# Juglans.net
KiCad netlist of a schematic drawn in Altium Designer
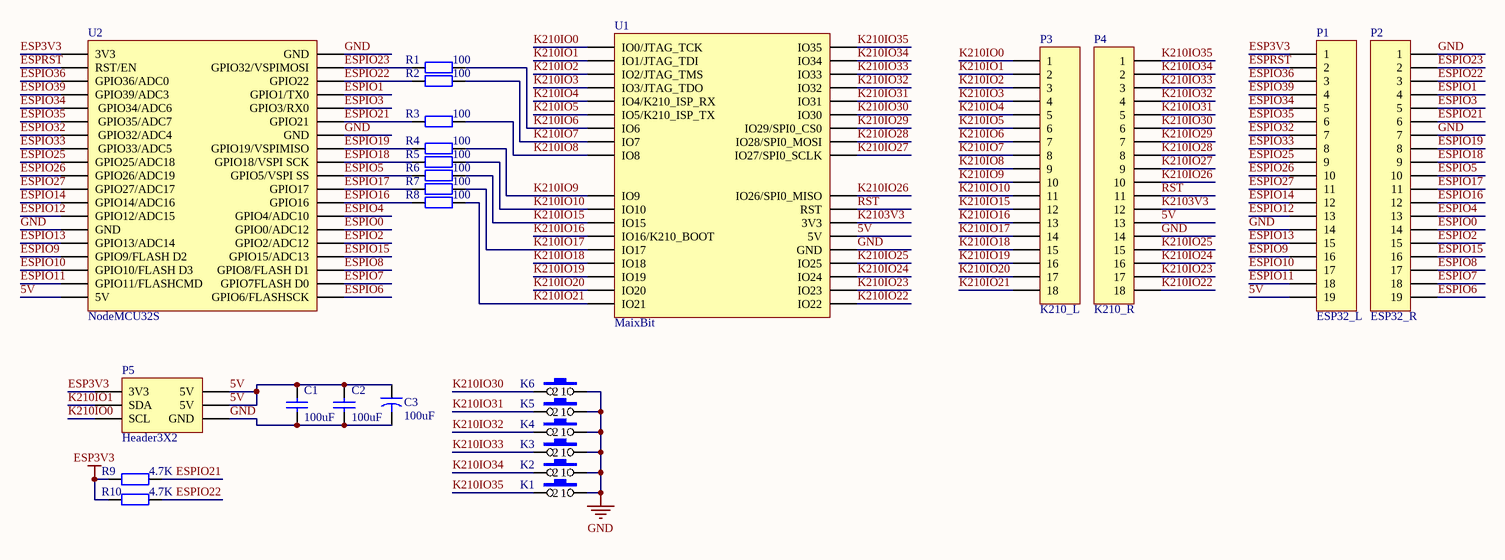
[diagram p0: Juglans.SchDoc]

(export (version "E")
  (design (tool "Eeschema 10.0.6"))
  (components
    (comp (ref "C1")
      (value "100uF")
      (footprint "C 1206_L")
      (description "Capacitor")
      (fields (field (name "Comment") "Cap") (field (name "PUBLISHER") "Altium Limited"))
      (libsource (lib "Miscellaneous Devices") (part "Cap"))
    )
    (comp (ref "C2")
      (value "100uF")
      (footprint "C 1206_L")
      (description "Capacitor")
      (fields (field (name "Comment") "Cap") (field (name "PUBLISHER") "Altium Limited"))
      (libsource (lib "Miscellaneous Devices") (part "Cap"))
    )
    (comp (ref "C3")
      (value "100uF")
      (footprint "CAP")
      (description "Capacitor")
      (fields (field (name "Comment") "Cap2") (field (name "PUBLISHER") "Altium Limited"))
      (libsource (lib "Miscellaneous Devices") (part "Cap2"))
    )
    (comp (ref "K1") (value "KEY?") (footprint "SW-PB2-S") (libsource (lib "Connectors") (part "SW-PB2")))
    (comp (ref "K2") (value "KEY?") (footprint "SW-PB2-S") (libsource (lib "Connectors") (part "SW-PB2")))
    (comp (ref "K3") (value "KEY?") (footprint "SW-PB2-S") (libsource (lib "Connectors") (part "SW-PB2")))
    (comp (ref "K4") (value "KEY?") (footprint "SW-PB2-S") (libsource (lib "Connectors") (part "SW-PB2")))
    (comp (ref "K5") (value "KEY?") (footprint "SW-PB2-S") (libsource (lib "Connectors") (part "SW-PB2")))
    (comp (ref "K6") (value "KEY?") (footprint "SW-PB2-S") (libsource (lib "Connectors") (part "SW-PB2")))
    (comp (ref "P1")
      (value "ESP32_L")
      (footprint "HDR1X19")
      (description "Header, 19-Pin")
      (fields (field (name "PUBLISHER") "Altium Limited"))
      (libsource (lib "") (part "Header 19_1"))
    )
    (comp (ref "P2")
      (value "ESP32_R")
      (footprint "HDR1X19")
      (description "Header, 19-Pin")
      (fields (field (name "PUBLISHER") "Altium Limited"))
      (libsource (lib "Miscellaneous Connectors") (part "Header 19"))
    )
    (comp (ref "P3")
      (value "K210_L")
      (footprint "HDR1X18")
      (description "Header, 18-Pin")
      (fields (field (name "PUBLISHER") "Altium Limited"))
      (libsource (lib "") (part "Header 18_1"))
    )
    (comp (ref "P4")
      (value "K210_R")
      (footprint "HDR1X18")
      (description "Header, 18-Pin")
      (fields (field (name "PUBLISHER") "Altium Limited"))
      (libsource (lib "Miscellaneous Connectors") (part "Header 18"))
    )
    (comp (ref "P5") (value "Header3X2") (footprint "Header3X2") (libsource (lib "Juglans") (part "H3X2")))
    (comp (ref "R1")
      (value "100")
      (footprint "R 0603_L")
      (description "Resistor")
      (fields (field (name "Comment") "Res2") (field (name "PUBLISHER") "Altium Limited"))
      (libsource (lib "Miscellaneous Devices") (part "Res2"))
    )
    (comp (ref "R2")
      (value "100")
      (footprint "R 0603_L")
      (description "Resistor")
      (fields (field (name "Comment") "Res2") (field (name "PUBLISHER") "Altium Limited"))
      (libsource (lib "Miscellaneous Devices") (part "Res2"))
    )
    (comp (ref "R3")
      (value "100")
      (footprint "R 0603_L")
      (description "Resistor")
      (fields (field (name "Comment") "Res2") (field (name "PUBLISHER") "Altium Limited"))
      (libsource (lib "Miscellaneous Devices") (part "Res2"))
    )
    (comp (ref "R4")
      (value "100")
      (footprint "R 0603_L")
      (description "Resistor")
      (fields (field (name "Comment") "Res2") (field (name "PUBLISHER") "Altium Limited"))
      (libsource (lib "Miscellaneous Devices") (part "Res2"))
    )
    (comp (ref "R5")
      (value "100")
      (footprint "R 0603_L")
      (description "Resistor")
      (fields (field (name "Comment") "Res2") (field (name "PUBLISHER") "Altium Limited"))
      (libsource (lib "Miscellaneous Devices") (part "Res2"))
    )
    (comp (ref "R6")
      (value "100")
      (footprint "R 0603_L")
      (description "Resistor")
      (fields (field (name "Comment") "Res2") (field (name "PUBLISHER") "Altium Limited"))
      (libsource (lib "Miscellaneous Devices") (part "Res2"))
    )
    (comp (ref "R7")
      (value "100")
      (footprint "R 0603_L")
      (description "Resistor")
      (fields (field (name "Comment") "Res2") (field (name "PUBLISHER") "Altium Limited"))
      (libsource (lib "Miscellaneous Devices") (part "Res2"))
    )
    (comp (ref "R8")
      (value "100")
      (footprint "R 0603_L")
      (description "Resistor")
      (fields (field (name "Comment") "Res2") (field (name "PUBLISHER") "Altium Limited"))
      (libsource (lib "Miscellaneous Devices") (part "Res2"))
    )
    (comp (ref "R9")
      (value "4.7K")
      (footprint "R 0603_L")
      (description "Resistor")
      (fields (field (name "Comment") "Res2") (field (name "PUBLISHER") "Altium Limited"))
      (libsource (lib "Miscellaneous Devices") (part "Res2"))
    )
    (comp (ref "R10")
      (value "4.7K")
      (footprint "R 0603_L")
      (description "Resistor")
      (fields (field (name "Comment") "Res2") (field (name "PUBLISHER") "Altium Limited"))
      (libsource (lib "Miscellaneous Devices") (part "Res2"))
    )
    (comp (ref "U1") (value "MaixBit") (footprint "MaixBit") (libsource (lib "Juglans") (part "MaixBit")))
    (comp (ref "U2")
      (value "NodeMCU32S")
      (footprint "NodeMCU32S")
      (libsource (lib "Juglans") (part "NodeMCU32S"))
    )
  )
  (nets
    (net (code "1") (name "/5V") (class "Default")
      (node (ref "C1") (pin "2") (pinfunction "2_2") (pintype "passive"))
      (node (ref "C2") (pin "2") (pinfunction "2_2") (pintype "passive"))
      (node (ref "C3") (pin "1") (pinfunction "1_1") (pintype "passive"))
      (node (ref "P1") (pin "19") (pinfunction "19_19") (pintype "passive"))
      (node (ref "P4") (pin "13") (pinfunction "13_13") (pintype "passive"))
      (node (ref "P5") (pin "2") (pinfunction "5V_2") (pintype "passive"))
      (node (ref "P5") (pin "4") (pinfunction "5V_4") (pintype "passive"))
      (node (ref "U1") (pin "23") (pinfunction "5V_23") (pintype "passive"))
      (node (ref "U2") (pin "18") (pinfunction "5V_18") (pintype "passive"))
    )
    (net (code "2") (name "/ESPIO0") (class "Default")
      (node (ref "P2") (pin "14") (pinfunction "14_14") (pintype "passive"))
      (node (ref "U2") (pin "24") (pinfunction "GPIO0/ADC12_24") (pintype "passive"))
    )
    (net (code "3") (name "/ESPIO1") (class "Default")
      (node (ref "P2") (pin "4") (pinfunction "4_4") (pintype "passive"))
      (node (ref "U2") (pin "34") (pinfunction "GPIO1/TX0_34") (pintype "passive"))
    )
    (net (code "4") (name "/ESPIO2") (class "Default")
      (node (ref "P2") (pin "15") (pinfunction "15_15") (pintype "passive"))
      (node (ref "U2") (pin "23") (pinfunction "GPIO2/ADC12_23") (pintype "passive"))
    )
    (net (code "5") (name "/ESPIO3") (class "Default")
      (node (ref "P2") (pin "5") (pinfunction "5_5") (pintype "passive"))
      (node (ref "U2") (pin "33") (pinfunction "GPIO3/RX0_33") (pintype "passive"))
    )
    (net (code "6") (name "/ESPIO4") (class "Default")
      (node (ref "P2") (pin "13") (pinfunction "13_13") (pintype "passive"))
      (node (ref "U2") (pin "25") (pinfunction "GPIO4/ADC10_25") (pintype "passive"))
    )
    (net (code "7") (name "/ESPIO5") (class "Default")
      (node (ref "P2") (pin "10") (pinfunction "10_10") (pintype "passive"))
      (node (ref "R6") (pin "2") (pinfunction "2_2") (pintype "passive"))
      (node (ref "U2") (pin "28") (pinfunction "GPIO5/VSPI_SS_28") (pintype "passive"))
    )
    (net (code "8") (name "/ESPIO6") (class "Default")
      (node (ref "P2") (pin "19") (pinfunction "19_19") (pintype "passive"))
      (node (ref "U2") (pin "19") (pinfunction "GPIO6/FLASHSCK_19") (pintype "passive"))
    )
    (net (code "9") (name "/ESPIO7") (class "Default")
      (node (ref "P2") (pin "18") (pinfunction "18_18") (pintype "passive"))
      (node (ref "U2") (pin "20") (pinfunction "GPIO7FLASH_D0_20") (pintype "passive"))
    )
    (net (code "10") (name "/ESPIO8") (class "Default")
      (node (ref "P2") (pin "17") (pinfunction "17_17") (pintype "passive"))
      (node (ref "U2") (pin "21") (pinfunction "GPIO8/FLASH_D1_21") (pintype "passive"))
    )
    (net (code "11") (name "/ESPIO9") (class "Default")
      (node (ref "P1") (pin "16") (pinfunction "16_16") (pintype "passive"))
      (node (ref "U2") (pin "15") (pinfunction "GPIO9/FLASH_D2_15") (pintype "passive"))
    )
    (net (code "12") (name "/ESPIO10") (class "Default")
      (node (ref "P1") (pin "17") (pinfunction "17_17") (pintype "passive"))
      (node (ref "U2") (pin "16") (pinfunction "GPIO10/FLASH_D3_16") (pintype "passive"))
    )
    (net (code "13") (name "/ESPIO11") (class "Default")
      (node (ref "P1") (pin "18") (pinfunction "18_18") (pintype "passive"))
      (node (ref "U2") (pin "17") (pinfunction "GPIO11/FLASHCMD_17") (pintype "passive"))
    )
    (net (code "14") (name "/ESPIO12") (class "Default")
      (node (ref "P1") (pin "13") (pinfunction "13_13") (pintype "passive"))
      (node (ref "U2") (pin "12") (pinfunction "GPIO12/ADC15_12") (pintype "passive"))
    )
    (net (code "15") (name "/ESPIO13") (class "Default")
      (node (ref "P1") (pin "15") (pinfunction "15_15") (pintype "passive"))
      (node (ref "U2") (pin "14") (pinfunction "GPIO13/ADC14_14") (pintype "passive"))
    )
    (net (code "16") (name "/ESPIO14") (class "Default")
      (node (ref "P1") (pin "12") (pinfunction "12_12") (pintype "passive"))
      (node (ref "U2") (pin "11") (pinfunction "GPIO14/ADC16_11") (pintype "passive"))
    )
    (net (code "17") (name "/ESPIO15") (class "Default")
      (node (ref "P2") (pin "16") (pinfunction "16_16") (pintype "passive"))
      (node (ref "U2") (pin "22") (pinfunction "GPIO15/ADC13_22") (pintype "passive"))
    )
    (net (code "18") (name "/ESPIO16") (class "Default")
      (node (ref "P2") (pin "12") (pinfunction "12_12") (pintype "passive"))
      (node (ref "R8") (pin "2") (pinfunction "2_2") (pintype "passive"))
      (node (ref "U2") (pin "26") (pinfunction "GPIO16_26") (pintype "passive"))
    )
    (net (code "19") (name "/ESPIO17") (class "Default")
      (node (ref "P2") (pin "11") (pinfunction "11_11") (pintype "passive"))
      (node (ref "R7") (pin "2") (pinfunction "2_2") (pintype "passive"))
      (node (ref "U2") (pin "27") (pinfunction "GPIO17_27") (pintype "passive"))
    )
    (net (code "20") (name "/ESPIO18") (class "Default")
      (node (ref "P2") (pin "9") (pinfunction "9_9") (pintype "passive"))
      (node (ref "R5") (pin "2") (pinfunction "2_2") (pintype "passive"))
      (node (ref "U2") (pin "29") (pinfunction "GPIO18/VSPI_SCK_29") (pintype "passive"))
    )
    (net (code "21") (name "/ESPIO19") (class "Default")
      (node (ref "P2") (pin "8") (pinfunction "8_8") (pintype "passive"))
      (node (ref "R4") (pin "2") (pinfunction "2_2") (pintype "passive"))
      (node (ref "U2") (pin "30") (pinfunction "GPIO19/VSPIMISO_30") (pintype "passive"))
    )
    (net (code "22") (name "/ESPIO21") (class "Default")
      (node (ref "P2") (pin "6") (pinfunction "6_6") (pintype "passive"))
      (node (ref "R3") (pin "2") (pinfunction "2_2") (pintype "passive"))
      (node (ref "R9") (pin "1") (pinfunction "1_1") (pintype "passive"))
      (node (ref "U2") (pin "32") (pinfunction "GPIO21_32") (pintype "passive"))
    )
    (net (code "23") (name "/ESPIO22") (class "Default")
      (node (ref "P2") (pin "3") (pinfunction "3_3") (pintype "passive"))
      (node (ref "R10") (pin "1") (pinfunction "1_1") (pintype "passive"))
      (node (ref "R2") (pin "2") (pinfunction "2_2") (pintype "passive"))
      (node (ref "U2") (pin "35") (pinfunction "GPIO22_35") (pintype "passive"))
    )
    (net (code "24") (name "/ESPIO23") (class "Default")
      (node (ref "P2") (pin "2") (pinfunction "2_2") (pintype "passive"))
      (node (ref "R1") (pin "2") (pinfunction "2_2") (pintype "passive"))
      (node (ref "U2") (pin "36") (pinfunction "GPIO32/VSPIMOSI_36") (pintype "passive"))
    )
    (net (code "25") (name "/ESPIO25") (class "Default")
      (node (ref "P1") (pin "9") (pinfunction "9_9") (pintype "passive"))
      (node (ref "U2") (pin "8") (pinfunction "GPIO25/ADC18_8") (pintype "passive"))
    )
    (net (code "26") (name "/ESPIO26") (class "Default")
      (node (ref "P1") (pin "10") (pinfunction "10_10") (pintype "passive"))
      (node (ref "U2") (pin "9") (pinfunction "GPIO26/ADC19_9") (pintype "passive"))
    )
    (net (code "27") (name "/ESPIO27") (class "Default")
      (node (ref "P1") (pin "11") (pinfunction "11_11") (pintype "passive"))
      (node (ref "U2") (pin "10") (pinfunction "GPIO27/ADC17_10") (pintype "passive"))
    )
    (net (code "28") (name "/ESPIO32") (class "Default")
      (node (ref "P1") (pin "7") (pinfunction "7_7") (pintype "passive"))
      (node (ref "U2") (pin "6") (pinfunction "_GPIO32/ADC4_6") (pintype "passive"))
    )
    (net (code "29") (name "/ESPIO33") (class "Default")
      (node (ref "P1") (pin "8") (pinfunction "8_8") (pintype "passive"))
      (node (ref "U2") (pin "7") (pinfunction "_GPIO33/ADC5_7") (pintype "passive"))
    )
    (net (code "30") (name "/ESPIO34") (class "Default")
      (node (ref "P1") (pin "5") (pinfunction "5_5") (pintype "passive"))
      (node (ref "U2") (pin "4") (pinfunction "_GPIO34/ADC6_4") (pintype "passive"))
    )
    (net (code "31") (name "/ESPIO35") (class "Default")
      (node (ref "P1") (pin "6") (pinfunction "6_6") (pintype "passive"))
      (node (ref "U2") (pin "5") (pinfunction "_GPIO35/ADC7_5") (pintype "passive"))
    )
    (net (code "32") (name "/ESPIO36") (class "Default")
      (node (ref "P1") (pin "3") (pinfunction "3_3") (pintype "passive"))
      (node (ref "U2") (pin "2") (pinfunction "GPIO36/ADC0_2") (pintype "passive"))
    )
    (net (code "33") (name "/ESPIO39") (class "Default")
      (node (ref "P1") (pin "4") (pinfunction "4_4") (pintype "passive"))
      (node (ref "U2") (pin "3") (pinfunction "GPIO39/ADC3_3") (pintype "passive"))
    )
    (net (code "34") (name "/ESPRST") (class "Default")
      (node (ref "P1") (pin "2") (pinfunction "2_2") (pintype "passive"))
      (node (ref "U2") (pin "1") (pinfunction "RST/EN_1") (pintype "passive"))
    )
    (net (code "35") (name "/K210IO0") (class "Default")
      (node (ref "P3") (pin "1") (pinfunction "1_1") (pintype "passive"))
      (node (ref "P5") (pin "5") (pinfunction "SCL_5") (pintype "passive"))
      (node (ref "U1") (pin "0") (pinfunction "IO0/JTAG_TCK_0") (pintype "passive"))
    )
    (net (code "36") (name "/K210IO1") (class "Default")
      (node (ref "P3") (pin "2") (pinfunction "2_2") (pintype "passive"))
      (node (ref "P5") (pin "3") (pinfunction "SDA_3") (pintype "passive"))
      (node (ref "U1") (pin "1") (pinfunction "IO1/JTAG_TDI_1") (pintype "passive"))
    )
    (net (code "37") (name "/K210IO2") (class "Default")
      (node (ref "P3") (pin "3") (pinfunction "3_3") (pintype "passive"))
      (node (ref "U1") (pin "2") (pinfunction "IO2/JTAG_TMS_2") (pintype "passive"))
    )
    (net (code "38") (name "/K210IO3") (class "Default")
      (node (ref "P3") (pin "4") (pinfunction "4_4") (pintype "passive"))
      (node (ref "U1") (pin "3") (pinfunction "IO3/JTAG_TDO_3") (pintype "passive"))
    )
    (net (code "39") (name "/K210IO4") (class "Default")
      (node (ref "P3") (pin "5") (pinfunction "5_5") (pintype "passive"))
      (node (ref "U1") (pin "4") (pinfunction "IO4/K210_ISP_RX_4") (pintype "passive"))
    )
    (net (code "40") (name "/K210IO5") (class "Default")
      (node (ref "P3") (pin "6") (pinfunction "6_6") (pintype "passive"))
      (node (ref "U1") (pin "5") (pinfunction "IO5/K210_ISP_TX_5") (pintype "passive"))
    )
    (net (code "41") (name "/K210IO6") (class "Default")
      (node (ref "P3") (pin "7") (pinfunction "7_7") (pintype "passive"))
      (node (ref "R1") (pin "1") (pinfunction "1_1") (pintype "passive"))
      (node (ref "U1") (pin "6") (pinfunction "IO6_6") (pintype "passive"))
    )
    (net (code "42") (name "/K210IO7") (class "Default")
      (node (ref "P3") (pin "8") (pinfunction "8_8") (pintype "passive"))
      (node (ref "R2") (pin "1") (pinfunction "1_1") (pintype "passive"))
      (node (ref "U1") (pin "7") (pinfunction "IO7_7") (pintype "passive"))
    )
    (net (code "43") (name "/K210IO8") (class "Default")
      (node (ref "P3") (pin "9") (pinfunction "9_9") (pintype "passive"))
      (node (ref "R3") (pin "1") (pinfunction "1_1") (pintype "passive"))
      (node (ref "U1") (pin "8") (pinfunction "IO8_8") (pintype "passive"))
    )
    (net (code "44") (name "/K210IO9") (class "Default")
      (node (ref "P3") (pin "10") (pinfunction "10_10") (pintype "passive"))
      (node (ref "R4") (pin "1") (pinfunction "1_1") (pintype "passive"))
      (node (ref "U1") (pin "9") (pinfunction "IO9_9") (pintype "passive"))
    )
    (net (code "45") (name "/K210IO10") (class "Default")
      (node (ref "P3") (pin "11") (pinfunction "11_11") (pintype "passive"))
      (node (ref "R5") (pin "1") (pinfunction "1_1") (pintype "passive"))
      (node (ref "U1") (pin "10") (pinfunction "IO10_10") (pintype "passive"))
    )
    (net (code "46") (name "/K210IO15") (class "Default")
      (node (ref "P3") (pin "12") (pinfunction "12_12") (pintype "passive"))
      (node (ref "R6") (pin "1") (pinfunction "1_1") (pintype "passive"))
      (node (ref "U1") (pin "11") (pinfunction "IO15_11") (pintype "passive"))
    )
    (net (code "47") (name "/K210IO16") (class "Default")
      (node (ref "P3") (pin "13") (pinfunction "13_13") (pintype "passive"))
      (node (ref "U1") (pin "12") (pinfunction "IO16/K210_BOOT_12") (pintype "passive"))
    )
    (net (code "48") (name "/K210IO17") (class "Default")
      (node (ref "P3") (pin "14") (pinfunction "14_14") (pintype "passive"))
      (node (ref "R7") (pin "1") (pinfunction "1_1") (pintype "passive"))
      (node (ref "U1") (pin "13") (pinfunction "IO17_13") (pintype "passive"))
    )
    (net (code "49") (name "/K210IO18") (class "Default")
      (node (ref "P3") (pin "15") (pinfunction "15_15") (pintype "passive"))
      (node (ref "U1") (pin "14") (pinfunction "IO18_14") (pintype "passive"))
    )
    (net (code "50") (name "/K210IO19") (class "Default")
      (node (ref "P3") (pin "16") (pinfunction "16_16") (pintype "passive"))
      (node (ref "U1") (pin "15") (pinfunction "IO19_15") (pintype "passive"))
    )
    (net (code "51") (name "/K210IO20") (class "Default")
      (node (ref "P3") (pin "17") (pinfunction "17_17") (pintype "passive"))
      (node (ref "U1") (pin "16") (pinfunction "IO20_16") (pintype "passive"))
    )
    (net (code "52") (name "/K210IO21") (class "Default")
      (node (ref "P3") (pin "18") (pinfunction "18_18") (pintype "passive"))
      (node (ref "R8") (pin "1") (pinfunction "1_1") (pintype "passive"))
      (node (ref "U1") (pin "17") (pinfunction "IO21_17") (pintype "passive"))
    )
    (net (code "53") (name "/K210IO22") (class "Default")
      (node (ref "P4") (pin "18") (pinfunction "18_18") (pintype "passive"))
      (node (ref "U1") (pin "18") (pinfunction "IO22_18") (pintype "passive"))
    )
    (net (code "54") (name "/K210IO23") (class "Default")
      (node (ref "P4") (pin "17") (pinfunction "17_17") (pintype "passive"))
      (node (ref "U1") (pin "19") (pinfunction "IO23_19") (pintype "passive"))
    )
    (net (code "55") (name "/K210IO24") (class "Default")
      (node (ref "P4") (pin "16") (pinfunction "16_16") (pintype "passive"))
      (node (ref "U1") (pin "20") (pinfunction "IO24_20") (pintype "passive"))
    )
    (net (code "56") (name "/K210IO25") (class "Default")
      (node (ref "P4") (pin "15") (pinfunction "15_15") (pintype "passive"))
      (node (ref "U1") (pin "21") (pinfunction "IO25_21") (pintype "passive"))
    )
    (net (code "57") (name "/K210IO26") (class "Default")
      (node (ref "P4") (pin "10") (pinfunction "10_10") (pintype "passive"))
      (node (ref "U1") (pin "26") (pinfunction "IO26/SPI0_MISO_26") (pintype "passive"))
    )
    (net (code "58") (name "/K210IO27") (class "Default")
      (node (ref "P4") (pin "9") (pinfunction "9_9") (pintype "passive"))
      (node (ref "U1") (pin "27") (pinfunction "IO27/SPI0_SCLK_27") (pintype "passive"))
    )
    (net (code "59") (name "/K210IO28") (class "Default")
      (node (ref "P4") (pin "8") (pinfunction "8_8") (pintype "passive"))
      (node (ref "U1") (pin "28") (pinfunction "IO28/SPI0_MOSI_28") (pintype "passive"))
    )
    (net (code "60") (name "/K210IO29") (class "Default")
      (node (ref "P4") (pin "7") (pinfunction "7_7") (pintype "passive"))
      (node (ref "U1") (pin "29") (pinfunction "IO29/SPI0_CS0_29") (pintype "passive"))
    )
    (net (code "61") (name "/K210IO30") (class "Default")
      (node (ref "K6") (pin "1") (pinfunction "1_1") (pintype "passive"))
      (node (ref "P4") (pin "6") (pinfunction "6_6") (pintype "passive"))
      (node (ref "U1") (pin "30") (pinfunction "IO30_30") (pintype "passive"))
    )
    (net (code "62") (name "/K210IO31") (class "Default")
      (node (ref "K5") (pin "1") (pinfunction "1_1") (pintype "passive"))
      (node (ref "P4") (pin "5") (pinfunction "5_5") (pintype "passive"))
      (node (ref "U1") (pin "31") (pinfunction "IO31_31") (pintype "passive"))
    )
    (net (code "63") (name "/K210IO32") (class "Default")
      (node (ref "K4") (pin "1") (pinfunction "1_1") (pintype "passive"))
      (node (ref "P4") (pin "4") (pinfunction "4_4") (pintype "passive"))
      (node (ref "U1") (pin "32") (pinfunction "IO32_32") (pintype "passive"))
    )
    (net (code "64") (name "/K210IO33") (class "Default")
      (node (ref "K3") (pin "1") (pinfunction "1_1") (pintype "passive"))
      (node (ref "P4") (pin "3") (pinfunction "3_3") (pintype "passive"))
      (node (ref "U1") (pin "33") (pinfunction "IO33_33") (pintype "passive"))
    )
    (net (code "65") (name "/K210IO34") (class "Default")
      (node (ref "K2") (pin "1") (pinfunction "1_1") (pintype "passive"))
      (node (ref "P4") (pin "2") (pinfunction "2_2") (pintype "passive"))
      (node (ref "U1") (pin "34") (pinfunction "IO34_34") (pintype "passive"))
    )
    (net (code "66") (name "/K210IO35") (class "Default")
      (node (ref "K1") (pin "1") (pinfunction "1_1") (pintype "passive"))
      (node (ref "P4") (pin "1") (pinfunction "1_1") (pintype "passive"))
      (node (ref "U1") (pin "35") (pinfunction "IO35_35") (pintype "passive"))
    )
    (net (code "67") (name "/K2103V3") (class "Default")
      (node (ref "P4") (pin "12") (pinfunction "12_12") (pintype "passive"))
      (node (ref "U1") (pin "24") (pinfunction "3V3_24") (pintype "passive"))
    )
    (net (code "68") (name "/RST") (class "Default")
      (node (ref "P4") (pin "11") (pinfunction "11_11") (pintype "passive"))
      (node (ref "U1") (pin "25") (pinfunction "RST_25") (pintype "passive"))
    )
    (net (code "69") (name "ESP3V3") (class "Default")
      (node (ref "P1") (pin "1") (pinfunction "1_1") (pintype "passive"))
      (node (ref "P5") (pin "1") (pinfunction "3V3_1") (pintype "passive"))
      (node (ref "R10") (pin "2") (pinfunction "2_2") (pintype "passive"))
      (node (ref "R9") (pin "2") (pinfunction "2_2") (pintype "passive"))
      (node (ref "U2") (pin "0") (pinfunction "3V3_0") (pintype "passive"))
    )
    (net (code "70") (name "GND") (class "Default")
      (node (ref "C1") (pin "1") (pinfunction "1_1") (pintype "passive"))
      (node (ref "C2") (pin "1") (pinfunction "1_1") (pintype "passive"))
      (node (ref "C3") (pin "2") (pinfunction "2_2") (pintype "passive"))
      (node (ref "K1") (pin "2") (pinfunction "2_2") (pintype "passive"))
      (node (ref "K2") (pin "2") (pinfunction "2_2") (pintype "passive"))
      (node (ref "K3") (pin "2") (pinfunction "2_2") (pintype "passive"))
      (node (ref "K4") (pin "2") (pinfunction "2_2") (pintype "passive"))
      (node (ref "K5") (pin "2") (pinfunction "2_2") (pintype "passive"))
      (node (ref "K6") (pin "2") (pinfunction "2_2") (pintype "passive"))
      (node (ref "P1") (pin "14") (pinfunction "14_14") (pintype "passive"))
      (node (ref "P2") (pin "1") (pinfunction "1_1") (pintype "passive"))
      (node (ref "P2") (pin "7") (pinfunction "7_7") (pintype "passive"))
      (node (ref "P4") (pin "14") (pinfunction "14_14") (pintype "passive"))
      (node (ref "P5") (pin "6") (pinfunction "GND_6") (pintype "passive"))
      (node (ref "U1") (pin "22") (pinfunction "GND_22") (pintype "passive"))
      (node (ref "U2") (pin "13") (pinfunction "GND_13") (pintype "passive"))
      (node (ref "U2") (pin "31") (pinfunction "GND_31") (pintype "passive"))
      (node (ref "U2") (pin "37") (pinfunction "GND_37") (pintype "passive"))
    )
  )
)
